# RC_filter.net
KiCad netlist of a schematic drawn in EAGLE
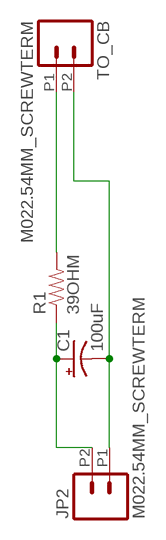
[diagram p0: schematic, sheet 1]

(export (version "E")
  (design (tool "Eeschema 10.0.6"))
  (components
    (comp (ref "C1")
      (value "100uF")
      (footprint "eagle-import:EIA7343")
      (libsource (lib "eagle-import") (part "100UF-10V-10%(TANT)"))
    )
    (comp (ref "JP2")
      (value "M022.54MM_SCREWTERM")
      (footprint "eagle-import:1X02_2.54_SCREWTERM")
      (libsource (lib "eagle-import") (part "M022.54MM_SCREWTERM"))
    )
    (comp (ref "R1")
      (value "39OHM")
      (footprint "eagle-import:0603")
      (libsource (lib "eagle-import") (part "33OHM1/10W1%(0603)"))
    )
    (comp (ref "TO_CB")
      (value "M022.54MM_SCREWTERM")
      (footprint "eagle-import:1X02_2.54_SCREWTERM")
      (libsource (lib "eagle-import") (part "M022.54MM_SCREWTERM"))
    )
  )
  (nets
    (net (code "1") (name "Net-(C1-+)") (class "Default")
      (node (ref "C1") (pin "A") (pinfunction "+_A") (pintype "passive"))
      (node (ref "JP2") (pin "P2") (pinfunction "2_P2") (pintype "passive"))
      (node (ref "R1") (pin "1") (pinfunction "1_1") (pintype "passive"))
    )
    (net (code "2") (name "Net-(C1--)") (class "Default")
      (node (ref "C1") (pin "C") (pinfunction "-_C") (pintype "passive"))
      (node (ref "JP2") (pin "P1") (pinfunction "1_P1") (pintype "passive"))
      (node (ref "TO_CB") (pin "P2") (pinfunction "2_P2") (pintype "passive"))
    )
    (net (code "3") (name "Net-(TO_CB-1)") (class "Default")
      (node (ref "R1") (pin "2") (pinfunction "2_2") (pintype "passive"))
      (node (ref "TO_CB") (pin "P1") (pinfunction "1_P1") (pintype "passive"))
    )
  )
)
